# legatus_v0_3.net
KiCad netlist of a schematic drawn in EAGLE
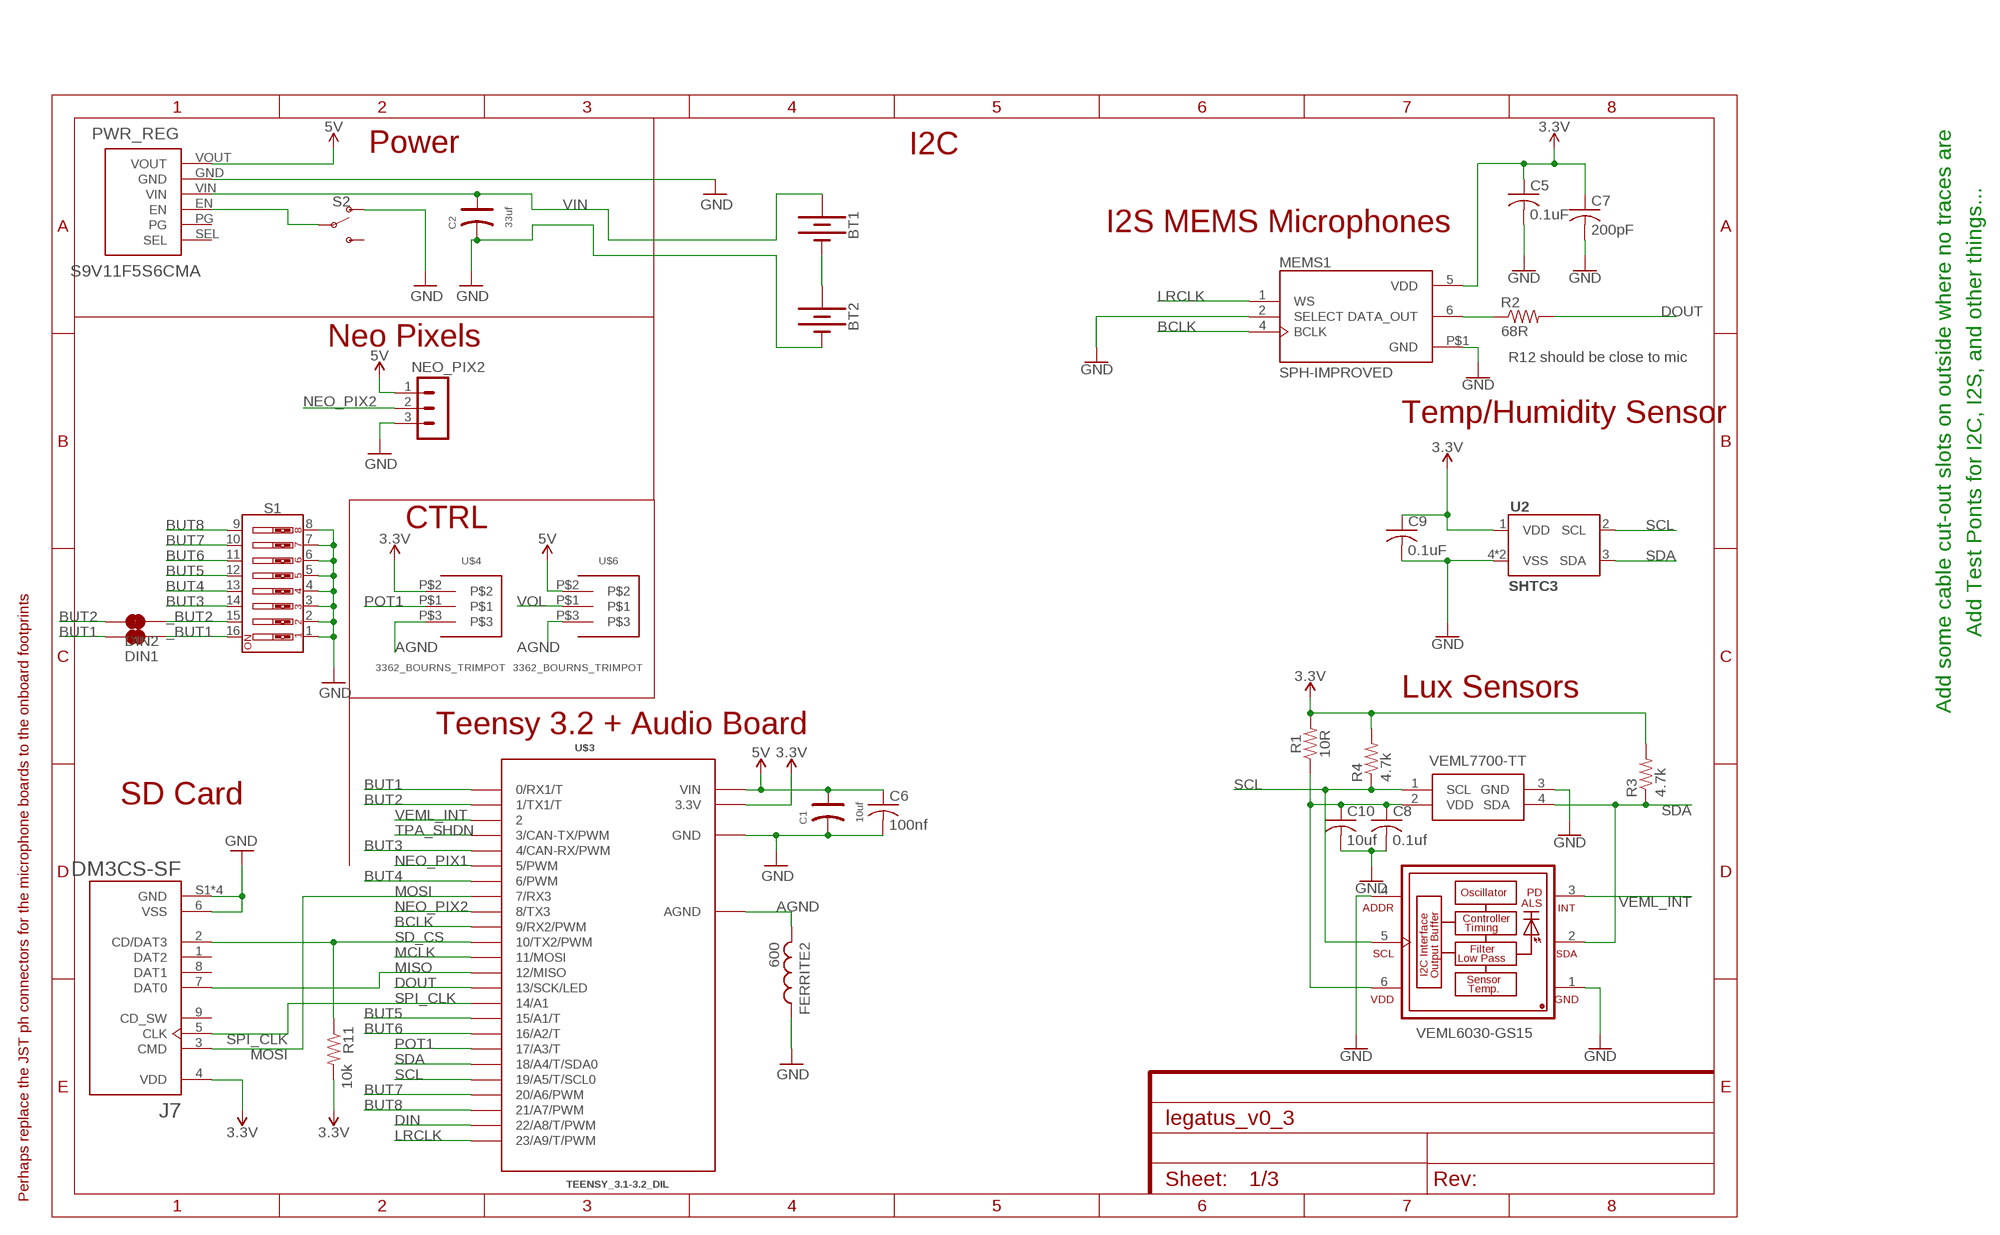
[diagram p0: schematic, sheet 1]
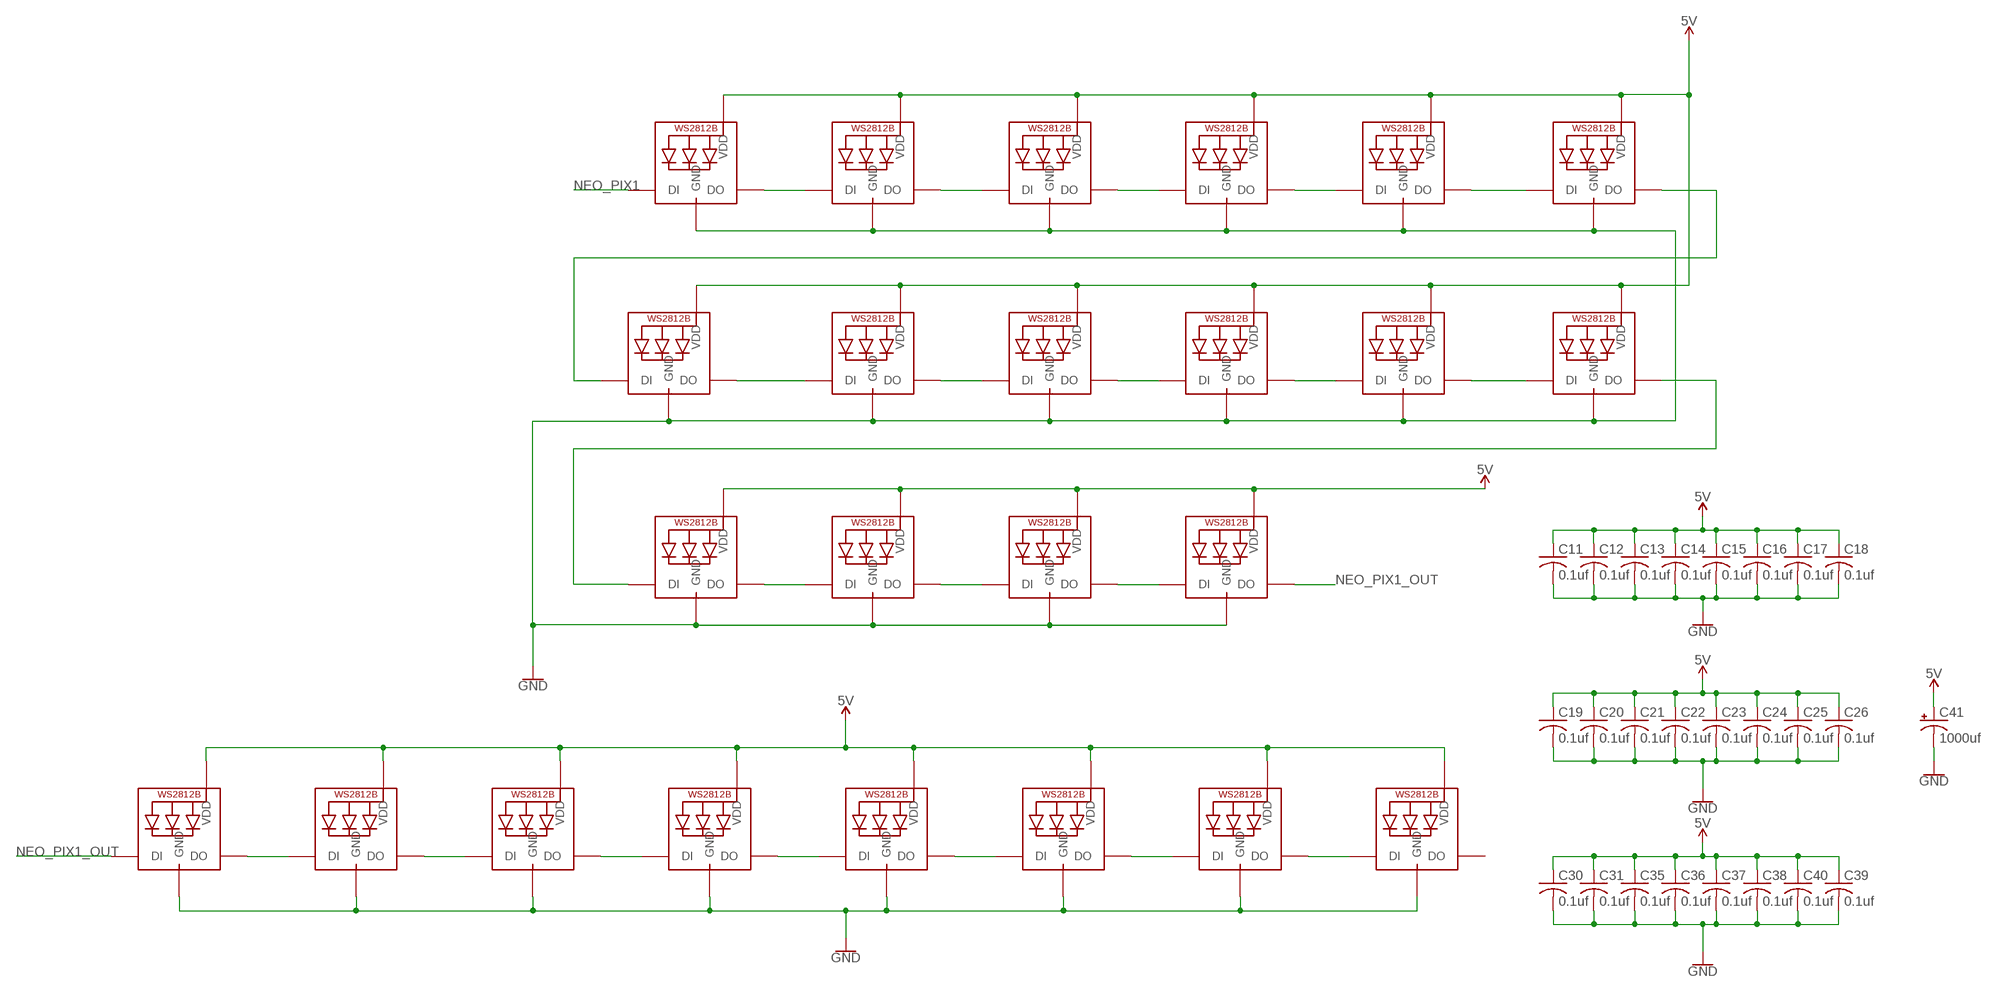
[diagram p1: schematic, sheet 2]
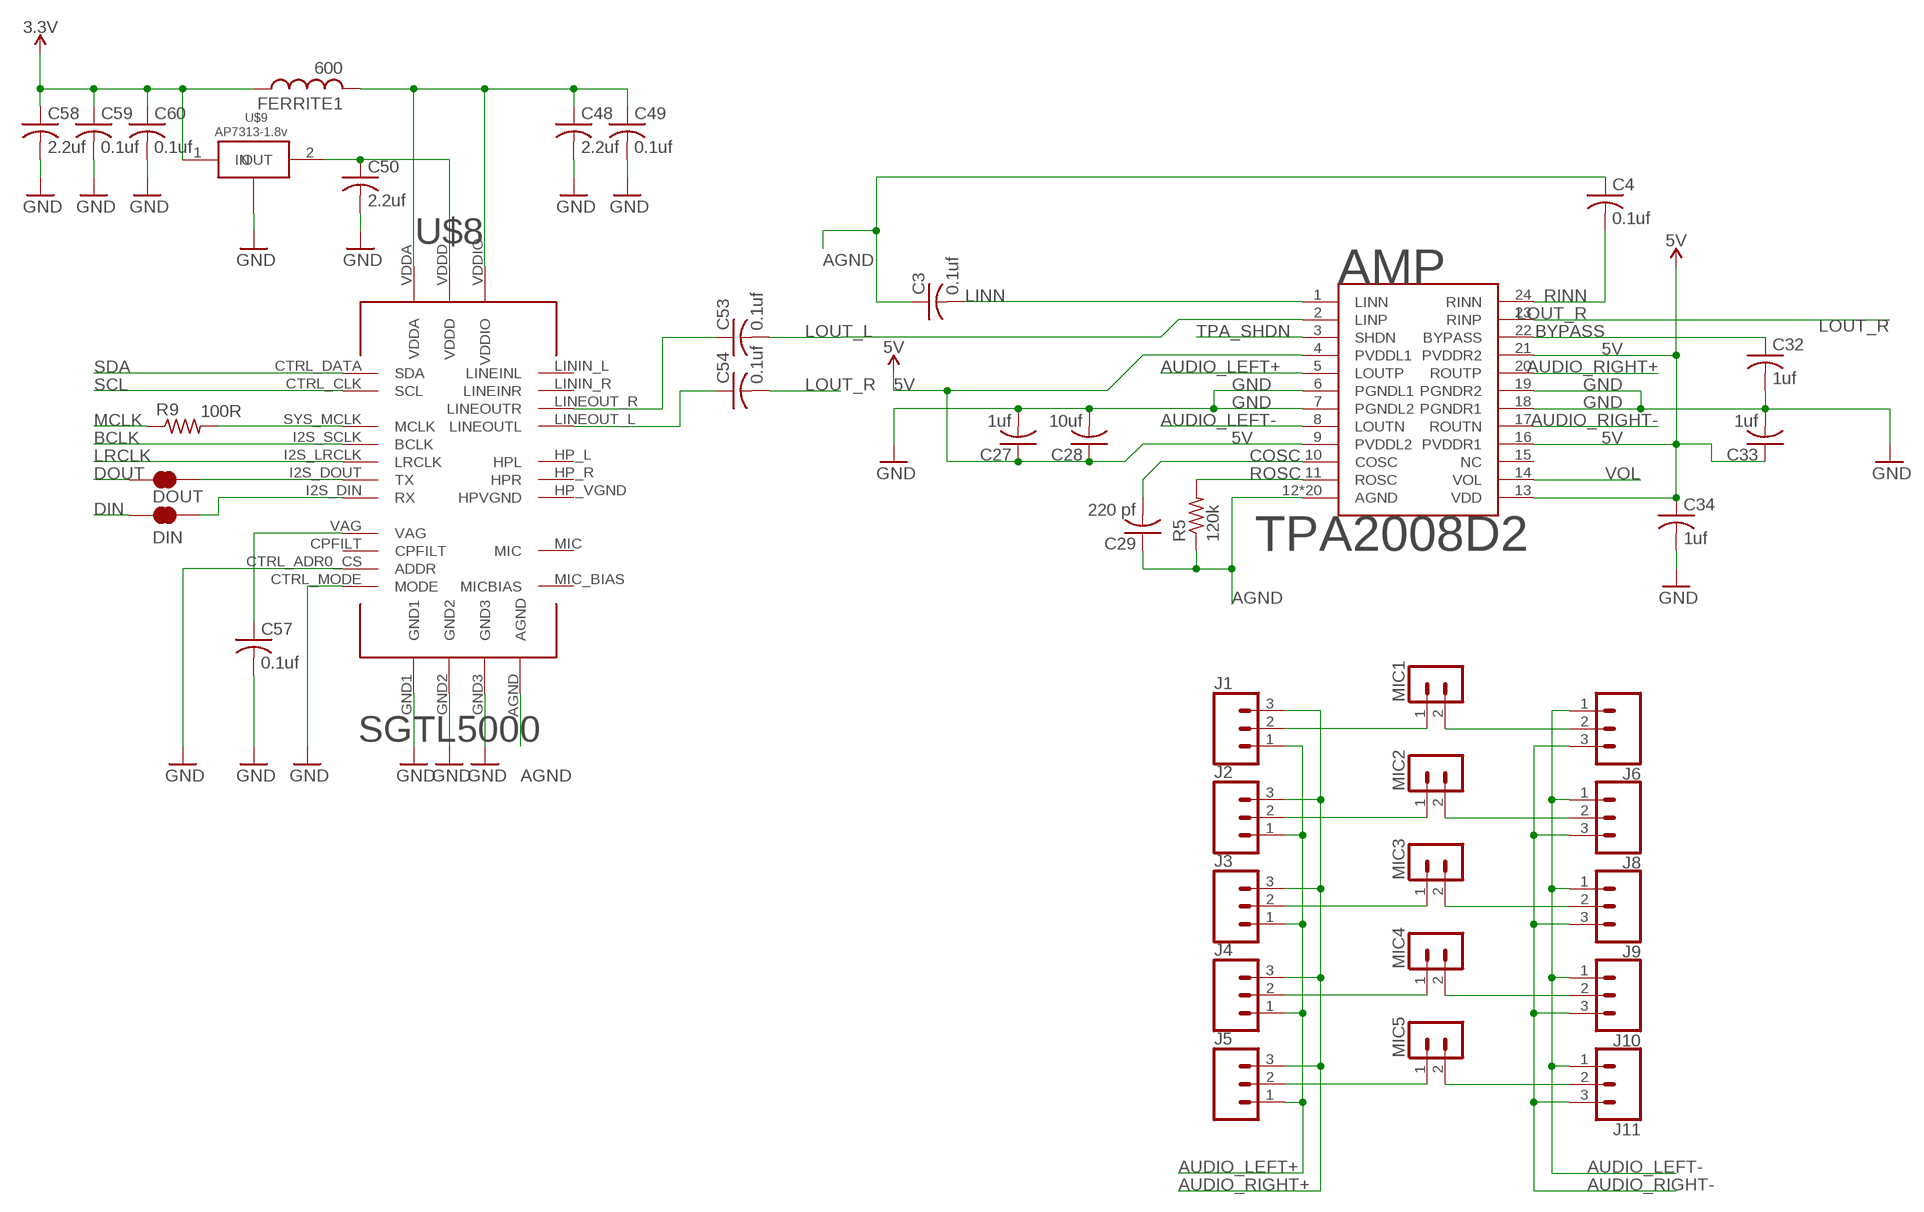
[diagram p2: schematic, sheet 3]

(export (version "E")
  (design (tool "Eeschema 10.0.6"))
  (components
    (comp (ref "AMP")
      (value "TPA2008D2")
      (footprint "eagle-import:PWP-TSSOP24")
      (libsource (lib "eagle-import") (part "TPA2008D2"))
    )
    (comp (ref "C3")
      (value "0.1uf")
      (footprint "eagle-import:C0805")
      (libsource (lib "eagle-import") (part "rcl_334_C-USC0805"))
    )
    (comp (ref "C4")
      (value "0.1uf")
      (footprint "eagle-import:C0805")
      (libsource (lib "eagle-import") (part "rcl_334_C-USC0805"))
    )
    (comp (ref "C27")
      (value "1uf")
      (footprint "eagle-import:C0805")
      (libsource (lib "eagle-import") (part "rcl_334_C-USC0805"))
    )
    (comp (ref "C28")
      (value "10uf")
      (footprint "eagle-import:C0805")
      (libsource (lib "eagle-import") (part "rcl_334_C-USC0805"))
    )
    (comp (ref "C29")
      (value "220 pf")
      (footprint "eagle-import:C0805")
      (libsource (lib "eagle-import") (part "rcl_334_C-USC0805"))
    )
    (comp (ref "C32")
      (value "1uf")
      (footprint "eagle-import:C0805")
      (libsource (lib "eagle-import") (part "rcl_334_C-USC0805"))
    )
    (comp (ref "C33")
      (value "1uf")
      (footprint "eagle-import:C0805")
      (libsource (lib "eagle-import") (part "rcl_334_C-USC0805"))
    )
    (comp (ref "C34")
      (value "1uf")
      (footprint "eagle-import:C0805")
      (libsource (lib "eagle-import") (part "rcl_334_C-USC0805"))
    )
    (comp (ref "C48")
      (value "2.2uf")
      (footprint "eagle-import:C0805")
      (libsource (lib "eagle-import") (part "rcl_334_C-USC0805"))
    )
    (comp (ref "C49")
      (value "0.1uf")
      (footprint "eagle-import:C0805")
      (libsource (lib "eagle-import") (part "rcl_334_C-USC0805"))
    )
    (comp (ref "C50")
      (value "2.2uf")
      (footprint "eagle-import:C0805")
      (libsource (lib "eagle-import") (part "rcl_334_C-USC0805"))
    )
    (comp (ref "C53")
      (value "0.1uf")
      (footprint "eagle-import:C0805")
      (libsource (lib "eagle-import") (part "rcl_334_C-USC0805"))
    )
    (comp (ref "C54")
      (value "0.1uf")
      (footprint "eagle-import:C0805")
      (libsource (lib "eagle-import") (part "rcl_334_C-USC0805"))
    )
    (comp (ref "C57")
      (value "0.1uf")
      (footprint "eagle-import:C0805")
      (libsource (lib "eagle-import") (part "rcl_334_C-USC0805"))
    )
    (comp (ref "C58")
      (value "2.2uf")
      (footprint "eagle-import:C0805")
      (libsource (lib "eagle-import") (part "rcl_334_C-USC0805"))
    )
    (comp (ref "C59")
      (value "0.1uf")
      (footprint "eagle-import:C0805")
      (libsource (lib "eagle-import") (part "rcl_334_C-USC0805"))
    )
    (comp (ref "C60")
      (value "0.1uf")
      (footprint "eagle-import:C0805")
      (libsource (lib "eagle-import") (part "rcl_334_C-USC0805"))
    )
    (comp (ref "DIN")
      (value "JUMPER-SMT_2_NC_TRACE_SILK")
      (footprint "eagle-import:SMT-JUMPER_2_NC_TRACE_SILK")
      (libsource (lib "eagle-import") (part "JUMPER-SMT_2_NC_TRACE_SILK"))
    )
    (comp (ref "DOUT")
      (value "JUMPER-SMT_2_NC_TRACE_SILK")
      (footprint "eagle-import:SMT-JUMPER_2_NC_TRACE_SILK")
      (libsource (lib "eagle-import") (part "JUMPER-SMT_2_NC_TRACE_SILK"))
    )
    (comp (ref "FERRITE1")
      (value "600")
      (footprint "eagle-import:RESC0805_N")
      (libsource (lib "eagle-import") (part "INDUCTOR_0805_N"))
    )
    (comp (ref "J1")
      (value "CONN_03")
      (footprint "eagle-import:1X03")
      (libsource (lib "eagle-import") (part "CONN_03"))
    )
    (comp (ref "J2")
      (value "CONN_03")
      (footprint "eagle-import:1X03")
      (libsource (lib "eagle-import") (part "CONN_03"))
    )
    (comp (ref "J3")
      (value "CONN_03")
      (footprint "eagle-import:1X03")
      (libsource (lib "eagle-import") (part "CONN_03"))
    )
    (comp (ref "J4")
      (value "CONN_03")
      (footprint "eagle-import:1X03")
      (libsource (lib "eagle-import") (part "CONN_03"))
    )
    (comp (ref "J5")
      (value "CONN_03")
      (footprint "eagle-import:1X03")
      (libsource (lib "eagle-import") (part "CONN_03"))
    )
    (comp (ref "J6")
      (value "CONN_03")
      (footprint "eagle-import:1X03")
      (libsource (lib "eagle-import") (part "CONN_03"))
    )
    (comp (ref "J8")
      (value "CONN_03")
      (footprint "eagle-import:1X03")
      (libsource (lib "eagle-import") (part "CONN_03"))
    )
    (comp (ref "J9")
      (value "CONN_03")
      (footprint "eagle-import:1X03")
      (libsource (lib "eagle-import") (part "CONN_03"))
    )
    (comp (ref "J10")
      (value "CONN_03")
      (footprint "eagle-import:1X03")
      (libsource (lib "eagle-import") (part "CONN_03"))
    )
    (comp (ref "J11")
      (value "CONN_03")
      (footprint "eagle-import:1X03")
      (libsource (lib "eagle-import") (part "CONN_03"))
    )
    (comp (ref "MIC1")
      (value "B2B-PH-K")
      (footprint "eagle-import:B2B-PH-K")
      (libsource (lib "eagle-import") (part "B2B-PH-K"))
    )
    (comp (ref "MIC2")
      (value "B2B-PH-K")
      (footprint "eagle-import:B2B-PH-K")
      (libsource (lib "eagle-import") (part "B2B-PH-K"))
    )
    (comp (ref "MIC3")
      (value "B2B-PH-K")
      (footprint "eagle-import:B2B-PH-K")
      (libsource (lib "eagle-import") (part "B2B-PH-K"))
    )
    (comp (ref "MIC4")
      (value "B2B-PH-K")
      (footprint "eagle-import:B2B-PH-K")
      (libsource (lib "eagle-import") (part "B2B-PH-K"))
    )
    (comp (ref "MIC5")
      (value "B2B-PH-K")
      (footprint "eagle-import:B2B-PH-K")
      (libsource (lib "eagle-import") (part "B2B-PH-K"))
    )
    (comp (ref "R5")
      (value "120k")
      (footprint "eagle-import:M0805")
      (libsource (lib "eagle-import") (part "R-US_M0805"))
    )
    (comp (ref "R9")
      (value "100R")
      (footprint "eagle-import:M0805")
      (libsource (lib "eagle-import") (part "rcl_R-US_M0805"))
    )
    (comp (ref "U$8")
      (value "SGTL5000")
      (footprint "eagle-import:QFN-32-5X5MM")
      (libsource (lib "eagle-import") (part "SGTL5000"))
    )
    (comp (ref "U$9")
      (value "AP7313-1.8v")
      (footprint "eagle-import:SOT-23")
      (libsource (lib "eagle-import") (part "AP7313"))
    )
    (comp (ref "C11")
      (value "0.1uf")
      (footprint "eagle-import:C0805")
      (libsource (lib "eagle-import") (part "rcl_334_C-USC0805"))
    )
    (comp (ref "C12")
      (value "0.1uf")
      (footprint "eagle-import:C0805")
      (libsource (lib "eagle-import") (part "rcl_334_C-USC0805"))
    )
    (comp (ref "C13")
      (value "0.1uf")
      (footprint "eagle-import:C0805")
      (libsource (lib "eagle-import") (part "rcl_334_C-USC0805"))
    )
    (comp (ref "C14")
      (value "0.1uf")
      (footprint "eagle-import:C0805")
      (libsource (lib "eagle-import") (part "rcl_334_C-USC0805"))
    )
    (comp (ref "C15")
      (value "0.1uf")
      (footprint "eagle-import:C0805")
      (libsource (lib "eagle-import") (part "rcl_334_C-USC0805"))
    )
    (comp (ref "C16")
      (value "0.1uf")
      (footprint "eagle-import:C0805")
      (libsource (lib "eagle-import") (part "rcl_334_C-USC0805"))
    )
    (comp (ref "C17")
      (value "0.1uf")
      (footprint "eagle-import:C0805")
      (libsource (lib "eagle-import") (part "rcl_334_C-USC0805"))
    )
    (comp (ref "C18")
      (value "0.1uf")
      (footprint "eagle-import:C0805")
      (libsource (lib "eagle-import") (part "rcl_334_C-USC0805"))
    )
    (comp (ref "C19")
      (value "0.1uf")
      (footprint "eagle-import:C0805")
      (libsource (lib "eagle-import") (part "rcl_334_C-USC0805"))
    )
    (comp (ref "C20")
      (value "0.1uf")
      (footprint "eagle-import:C0805")
      (libsource (lib "eagle-import") (part "rcl_334_C-USC0805"))
    )
    (comp (ref "C21")
      (value "0.1uf")
      (footprint "eagle-import:C0805")
      (libsource (lib "eagle-import") (part "rcl_334_C-USC0805"))
    )
    (comp (ref "C22")
      (value "0.1uf")
      (footprint "eagle-import:C0805")
      (libsource (lib "eagle-import") (part "rcl_334_C-USC0805"))
    )
    (comp (ref "C23")
      (value "0.1uf")
      (footprint "eagle-import:C0805")
      (libsource (lib "eagle-import") (part "rcl_334_C-USC0805"))
    )
    (comp (ref "C24")
      (value "0.1uf")
      (footprint "eagle-import:C0805")
      (libsource (lib "eagle-import") (part "rcl_334_C-USC0805"))
    )
    (comp (ref "C25")
      (value "0.1uf")
      (footprint "eagle-import:C0805")
      (libsource (lib "eagle-import") (part "rcl_334_C-USC0805"))
    )
    (comp (ref "C26")
      (value "0.1uf")
      (footprint "eagle-import:C0805")
      (libsource (lib "eagle-import") (part "rcl_334_C-USC0805"))
    )
    (comp (ref "C30")
      (value "0.1uf")
      (footprint "eagle-import:C0805")
      (libsource (lib "eagle-import") (part "rcl_334_C-USC0805"))
    )
    (comp (ref "C31")
      (value "0.1uf")
      (footprint "eagle-import:C0805")
      (libsource (lib "eagle-import") (part "rcl_334_C-USC0805"))
    )
    (comp (ref "C35")
      (value "0.1uf")
      (footprint "eagle-import:C0805")
      (libsource (lib "eagle-import") (part "rcl_334_C-USC0805"))
    )
    (comp (ref "C36")
      (value "0.1uf")
      (footprint "eagle-import:C0805")
      (libsource (lib "eagle-import") (part "rcl_334_C-USC0805"))
    )
    (comp (ref "C37")
      (value "0.1uf")
      (footprint "eagle-import:C0805")
      (libsource (lib "eagle-import") (part "rcl_334_C-USC0805"))
    )
    (comp (ref "C38")
      (value "0.1uf")
      (footprint "eagle-import:C0805")
      (libsource (lib "eagle-import") (part "rcl_334_C-USC0805"))
    )
    (comp (ref "C39")
      (value "0.1uf")
      (footprint "eagle-import:C0805")
      (libsource (lib "eagle-import") (part "rcl_334_C-USC0805"))
    )
    (comp (ref "C40")
      (value "0.1uf")
      (footprint "eagle-import:C0805")
      (libsource (lib "eagle-import") (part "rcl_334_C-USC0805"))
    )
    (comp (ref "C41")
      (value "1000uf")
      (footprint "eagle-import:153CLV-1010")
      (libsource (lib "eagle-import") (part "CPOL-US153CLV-1010"))
    )
    (comp (ref "LED1")
      (value "WS2812B_5050N")
      (footprint "eagle-import:WS2812B-NARROW")
      (libsource (lib "eagle-import") (part "WS2812B_5050N"))
    )
    (comp (ref "LED2")
      (value "WS2812B_5050N")
      (footprint "eagle-import:WS2812B-NARROW")
      (libsource (lib "eagle-import") (part "WS2812B_5050N"))
    )
    (comp (ref "LED3")
      (value "WS2812B_5050N")
      (footprint "eagle-import:WS2812B-NARROW")
      (libsource (lib "eagle-import") (part "WS2812B_5050N"))
    )
    (comp (ref "LED4")
      (value "WS2812B_5050N")
      (footprint "eagle-import:WS2812B-NARROW")
      (libsource (lib "eagle-import") (part "WS2812B_5050N"))
    )
    (comp (ref "LED5")
      (value "WS2812B_5050N")
      (footprint "eagle-import:WS2812B-NARROW")
      (libsource (lib "eagle-import") (part "WS2812B_5050N"))
    )
    (comp (ref "LED6")
      (value "WS2812B_5050N")
      (footprint "eagle-import:WS2812B-NARROW")
      (libsource (lib "eagle-import") (part "WS2812B_5050N"))
    )
    (comp (ref "LED7")
      (value "WS2812B_5050N")
      (footprint "eagle-import:WS2812B-NARROW")
      (libsource (lib "eagle-import") (part "WS2812B_5050N"))
    )
    (comp (ref "LED8")
      (value "WS2812B_5050N")
      (footprint "eagle-import:WS2812B-NARROW")
      (libsource (lib "eagle-import") (part "WS2812B_5050N"))
    )
    (comp (ref "LED9")
      (value "WS2812B_5050N")
      (footprint "eagle-import:WS2812B-NARROW")
      (libsource (lib "eagle-import") (part "WS2812B_5050N"))
    )
    (comp (ref "LED10")
      (value "WS2812B_5050N")
      (footprint "eagle-import:WS2812B-NARROW")
      (libsource (lib "eagle-import") (part "WS2812B_5050N"))
    )
    (comp (ref "LED11")
      (value "WS2812B_5050N")
      (footprint "eagle-import:WS2812B-NARROW")
      (libsource (lib "eagle-import") (part "WS2812B_5050N"))
    )
    (comp (ref "LED12")
      (value "WS2812B_5050N")
      (footprint "eagle-import:WS2812B-NARROW")
      (libsource (lib "eagle-import") (part "WS2812B_5050N"))
    )
    (comp (ref "LED13")
      (value "WS2812B_5050N")
      (footprint "eagle-import:WS2812B-NARROW")
      (libsource (lib "eagle-import") (part "WS2812B_5050N"))
    )
    (comp (ref "LED14")
      (value "WS2812B_5050N")
      (footprint "eagle-import:WS2812B-NARROW")
      (libsource (lib "eagle-import") (part "WS2812B_5050N"))
    )
    (comp (ref "LED15")
      (value "WS2812B_5050N")
      (footprint "eagle-import:WS2812B-NARROW")
      (libsource (lib "eagle-import") (part "WS2812B_5050N"))
    )
    (comp (ref "LED16")
      (value "WS2812B_5050N")
      (footprint "eagle-import:WS2812B-NARROW")
      (libsource (lib "eagle-import") (part "WS2812B_5050N"))
    )
    (comp (ref "LED17")
      (value "WS2812B_5050N")
      (footprint "eagle-import:WS2812B-NARROW")
      (libsource (lib "eagle-import") (part "WS2812B_5050N"))
    )
    (comp (ref "LED18")
      (value "WS2812B_5050N")
      (footprint "eagle-import:WS2812B-NARROW")
      (libsource (lib "eagle-import") (part "WS2812B_5050N"))
    )
    (comp (ref "LED19")
      (value "WS2812B_5050N")
      (footprint "eagle-import:WS2812B-NARROW")
      (libsource (lib "eagle-import") (part "WS2812B_5050N"))
    )
    (comp (ref "LED20")
      (value "WS2812B_5050N")
      (footprint "eagle-import:WS2812B-NARROW")
      (libsource (lib "eagle-import") (part "WS2812B_5050N"))
    )
    (comp (ref "LED21")
      (value "WS2812B_5050N")
      (footprint "eagle-import:WS2812B-NARROW")
      (libsource (lib "eagle-import") (part "WS2812B_5050N"))
    )
    (comp (ref "LED22")
      (value "WS2812B_5050N")
      (footprint "eagle-import:WS2812B-NARROW")
      (libsource (lib "eagle-import") (part "WS2812B_5050N"))
    )
    (comp (ref "LED23")
      (value "WS2812B_5050N")
      (footprint "eagle-import:WS2812B-NARROW")
      (libsource (lib "eagle-import") (part "WS2812B_5050N"))
    )
    (comp (ref "LED24")
      (value "WS2812B_5050N")
      (footprint "eagle-import:WS2812B-NARROW")
      (libsource (lib "eagle-import") (part "WS2812B_5050N"))
    )
    (comp (ref "BT1")
      (value "BATTERY-18650")
      (footprint "eagle-import:BATTERY_18650-HOLDER")
      (libsource (lib "eagle-import") (part "BATTERY-18650"))
    )
    (comp (ref "BT2")
      (value "BATTERY-18650")
      (footprint "eagle-import:BATTERY_18650-HOLDER")
      (libsource (lib "eagle-import") (part "BATTERY-18650"))
    )
    (comp (ref "C1")
      (value "10uf")
      (footprint "eagle-import:PC-D5.3MM")
      (fields (field (name "MPN") "KS 100uF/16V"))
      (libsource (lib "eagle-import") (part "DIP-ALUMINUM-47UF-16V(D5-H7MM)"))
    )
    (comp (ref "C2")
      (value "33uf")
      (footprint "eagle-import:PC-D5.3MM")
      (fields (field (name "MPN") "KS 100uF/16V"))
      (libsource (lib "eagle-import") (part "DIP-ALUMINUM-47UF-16V(D5-H7MM)"))
    )
    (comp (ref "C5")
      (value "0.1uF")
      (footprint "eagle-import:C0805")
      (libsource (lib "eagle-import") (part "rcl_334_C-USC0805"))
    )
    (comp (ref "C6")
      (value "100nf")
      (footprint "eagle-import:C2012")
      (libsource (lib "eagle-import") (part "C-USC2012"))
    )
    (comp (ref "C7")
      (value "200pF")
      (footprint "eagle-import:C0805")
      (libsource (lib "eagle-import") (part "rcl_334_C-USC0805"))
    )
    (comp (ref "C8")
      (value "0.1uf")
      (footprint "eagle-import:C0805")
      (libsource (lib "eagle-import") (part "rcl_334_C-USC0805"))
    )
    (comp (ref "C9")
      (value "0.1uF")
      (footprint "eagle-import:C0805")
      (libsource (lib "eagle-import") (part "rcl_334_C-USC0805"))
    )
    (comp (ref "C10")
      (value "10uf")
      (footprint "eagle-import:C0805")
      (libsource (lib "eagle-import") (part "rcl_334_C-USC0805"))
    )
    (comp (ref "DIN1")
      (value "JUMPER-SMT_2_NC_TRACE_SILK")
      (footprint "eagle-import:SMT-JUMPER_2_NC_TRACE_SILK")
      (libsource (lib "eagle-import") (part "JUMPER-SMT_2_NC_TRACE_SILK"))
    )
    (comp (ref "DIN2")
      (value "JUMPER-SMT_2_NC_TRACE_SILK")
      (footprint "eagle-import:SMT-JUMPER_2_NC_TRACE_SILK")
      (libsource (lib "eagle-import") (part "JUMPER-SMT_2_NC_TRACE_SILK"))
    )
    (comp (ref "FERRITE2")
      (value "600")
      (footprint "eagle-import:RESC0805_N")
      (libsource (lib "eagle-import") (part "INDUCTOR_0805_N"))
    )
    (comp (ref "J7")
      (value "DM3CS-SF")
      (footprint "eagle-import:HRS_DM3CS-SF")
      (fields (field (name "MF") "Hirose"))
      (libsource (lib "eagle-import") (part "DM3CS-SF"))
    )
    (comp (ref "MEMS1")
      (value "SPH-IMPROVED")
      (footprint "eagle-import:MIC_SPH0645LM4H-B_LARGER_RING")
      (libsource (lib "eagle-import") (part "SPH-IMPROVED"))
    )
    (comp (ref "NEO_PIX2")
      (value "B3B-PH-K")
      (footprint "eagle-import:B3B-PH-K")
      (libsource (lib "eagle-import") (part "B3B-PH-K"))
    )
    (comp (ref "PWR_REG")
      (value "S9V11F5S6CMA")
      (footprint "eagle-import:S9V11F3S5CMA")
      (libsource (lib "eagle-import") (part "S9V11F5S6CMA"))
    )
    (comp (ref "R1")
      (value "10R")
      (footprint "eagle-import:R0805")
      (libsource (lib "eagle-import") (part "audio amplifier example_970892_R-US_R0805"))
    )
    (comp (ref "R2")
      (value "68R")
      (footprint "eagle-import:M0805")
      (libsource (lib "eagle-import") (part "R-US_M0805"))
    )
    (comp (ref "R3")
      (value "4.7k")
      (footprint "eagle-import:M0805")
      (libsource (lib "eagle-import") (part "R-US_M0805"))
    )
    (comp (ref "R4")
      (value "4.7k")
      (footprint "eagle-import:M0805")
      (libsource (lib "eagle-import") (part "R-US_M0805"))
    )
    (comp (ref "R11")
      (value "10k")
      (footprint "eagle-import:M0805")
      (libsource (lib "eagle-import") (part "rcl_R-US_M0805"))
    )
    (comp (ref "S1")
      (value "DIP-08-PTH")
      (footprint "eagle-import:DIPSWITCH-08")
      (libsource (lib "eagle-import") (part "DIP-08-PTH"))
    )
    (comp (ref "S2")
      (value "SWITCH-SPDT-PTH-11.6X4.0MM-LOCK")
      (footprint "eagle-import:SWITCH_SPDT_PTH_11.6X4.0MM_LOCK")
      (libsource (lib "eagle-import") (part "SWITCH-SPDT-PTH-11.6X4.0MM-LOCK"))
    )
    (comp (ref "U$3")
      (value "TEENSY_3.1-3.2_DIL")
      (footprint "eagle-import:TEENSY_3.0-3.2&LC_DIL")
      (libsource (lib "eagle-import") (part "TEENSY_3.1-3.2_DIL"))
    )
    (comp (ref "U$4")
      (value "3362_BOURNS_TRIMPOT")
      (footprint "eagle-import:3362_BOURNS_TRIMPOT")
      (libsource (lib "eagle-import") (part "3362_BOURNS_TRIMPOT"))
    )
    (comp (ref "U$6")
      (value "3362_BOURNS_TRIMPOT")
      (footprint "eagle-import:3362_BOURNS_TRIMPOT")
      (libsource (lib "eagle-import") (part "3362_BOURNS_TRIMPOT"))
    )
    (comp (ref "U2")
      (value "SHTC3")
      (footprint "eagle-import:SHTC3")
      (libsource (lib "eagle-import") (part "SHTC3"))
    )
    (comp (ref "VEML1")
      (value "VEML7700-TT")
      (footprint "eagle-import:VEML7700")
      (fields (field (name "MOUSER_PART_NUMBER") "78-VEML7700-TT") (field (name "RS_PART_NUMBER") "1226791P"))
      (libsource (lib "eagle-import") (part "VEML7700-TT"))
    )
    (comp (ref "VMEL1")
      (value "VEML6030-GS15")
      (footprint "eagle-import:VISHAY_VEML6030_2X2X0.87")
      (fields (field (name "MF") "Vishay Semiconductor"))
      (libsource (lib "eagle-import") (part "VEML6030-GS15"))
    )
  )
  (nets
    (net (code "1") (name "3.3V") (class "Default")
      (node (ref "C5") (pin "1") (pinfunction "1_1") (pintype "passive"))
      (node (ref "C58") (pin "1") (pinfunction "1_1") (pintype "passive"))
      (node (ref "C59") (pin "1") (pinfunction "1_1") (pintype "passive"))
      (node (ref "C60") (pin "1") (pinfunction "1_1") (pintype "passive"))
      (node (ref "C7") (pin "1") (pinfunction "1_1") (pintype "passive"))
      (node (ref "C9") (pin "1") (pinfunction "1_1") (pintype "passive"))
      (node (ref "FERRITE1") (pin "1") (pinfunction "1_1") (pintype "passive"))
      (node (ref "J7") (pin "4") (pinfunction "VDD_4") (pintype "passive"))
      (node (ref "MEMS1") (pin "5") (pinfunction "VDD_5") (pintype "power_in"))
      (node (ref "R1") (pin "2") (pinfunction "2_2") (pintype "passive"))
      (node (ref "R11") (pin "2") (pinfunction "2_2") (pintype "passive"))
      (node (ref "R3") (pin "2") (pinfunction "2_2") (pintype "passive"))
      (node (ref "R4") (pin "2") (pinfunction "2_2") (pintype "passive"))
      (node (ref "U$3") (pin "3.3V") (pinfunction "3.3V_3.3V") (pintype "power_in"))
      (node (ref "U$4") (pin "P$2") (pinfunction "P$2_P$2") (pintype "bidirectional"))
      (node (ref "U$9") (pin "1") (pinfunction "IN_1") (pintype "bidirectional"))
      (node (ref "U2") (pin "1") (pinfunction "VDD_1") (pintype "bidirectional"))
    )
    (net (code "2") (name "5V") (class "Default")
      (node (ref "AMP") (pin "13") (pinfunction "VDD_13") (pintype "bidirectional"))
      (node (ref "AMP") (pin "16") (pinfunction "PVDDR1_16") (pintype "bidirectional"))
      (node (ref "AMP") (pin "21") (pinfunction "PVDDR2_21") (pintype "bidirectional"))
      (node (ref "AMP") (pin "4") (pinfunction "PVDDL1_4") (pintype "bidirectional"))
      (node (ref "AMP") (pin "9") (pinfunction "PVDDL2_9") (pintype "bidirectional"))
      (node (ref "C1") (pin "+") (pinfunction "+_+") (pintype "passive"))
      (node (ref "C11") (pin "1") (pinfunction "1_1") (pintype "passive"))
      (node (ref "C12") (pin "1") (pinfunction "1_1") (pintype "passive"))
      (node (ref "C13") (pin "1") (pinfunction "1_1") (pintype "passive"))
      (node (ref "C14") (pin "1") (pinfunction "1_1") (pintype "passive"))
      (node (ref "C15") (pin "1") (pinfunction "1_1") (pintype "passive"))
      (node (ref "C16") (pin "1") (pinfunction "1_1") (pintype "passive"))
      (node (ref "C17") (pin "1") (pinfunction "1_1") (pintype "passive"))
      (node (ref "C18") (pin "1") (pinfunction "1_1") (pintype "passive"))
      (node (ref "C19") (pin "1") (pinfunction "1_1") (pintype "passive"))
      (node (ref "C20") (pin "1") (pinfunction "1_1") (pintype "passive"))
      (node (ref "C21") (pin "1") (pinfunction "1_1") (pintype "passive"))
      (node (ref "C22") (pin "1") (pinfunction "1_1") (pintype "passive"))
      (node (ref "C23") (pin "1") (pinfunction "1_1") (pintype "passive"))
      (node (ref "C24") (pin "1") (pinfunction "1_1") (pintype "passive"))
      (node (ref "C25") (pin "1") (pinfunction "1_1") (pintype "passive"))
      (node (ref "C26") (pin "1") (pinfunction "1_1") (pintype "passive"))
      (node (ref "C27") (pin "1") (pinfunction "1_1") (pintype "passive"))
      (node (ref "C28") (pin "1") (pinfunction "1_1") (pintype "passive"))
      (node (ref "C30") (pin "1") (pinfunction "1_1") (pintype "passive"))
      (node (ref "C31") (pin "1") (pinfunction "1_1") (pintype "passive"))
      (node (ref "C33") (pin "1") (pinfunction "1_1") (pintype "passive"))
      (node (ref "C34") (pin "1") (pinfunction "1_1") (pintype "passive"))
      (node (ref "C35") (pin "1") (pinfunction "1_1") (pintype "passive"))
      (node (ref "C36") (pin "1") (pinfunction "1_1") (pintype "passive"))
      (node (ref "C37") (pin "1") (pinfunction "1_1") (pintype "passive"))
      (node (ref "C38") (pin "1") (pinfunction "1_1") (pintype "passive"))
      (node (ref "C39") (pin "1") (pinfunction "1_1") (pintype "passive"))
      (node (ref "C40") (pin "1") (pinfunction "1_1") (pintype "passive"))
      (node (ref "C41") (pin "+") (pinfunction "+_+") (pintype "passive"))
      (node (ref "C6") (pin "1") (pinfunction "1_1") (pintype "passive"))
      (node (ref "LED1") (pin "1-VDD") (pinfunction "VDD_1-VDD") (pintype "power_in"))
      (node (ref "LED10") (pin "1-VDD") (pinfunction "VDD_1-VDD") (pintype "power_in"))
      (node (ref "LED11") (pin "1-VDD") (pinfunction "VDD_1-VDD") (pintype "power_in"))
      (node (ref "LED12") (pin "1-VDD") (pinfunction "VDD_1-VDD") (pintype "power_in"))
      (node (ref "LED13") (pin "1-VDD") (pinfunction "VDD_1-VDD") (pintype "power_in"))
      (node (ref "LED14") (pin "1-VDD") (pinfunction "VDD_1-VDD") (pintype "power_in"))
      (node (ref "LED15") (pin "1-VDD") (pinfunction "VDD_1-VDD") (pintype "power_in"))
      (node (ref "LED16") (pin "1-VDD") (pinfunction "VDD_1-VDD") (pintype "power_in"))
      (node (ref "LED17") (pin "1-VDD") (pinfunction "VDD_1-VDD") (pintype "power_in"))
      (node (ref "LED18") (pin "1-VDD") (pinfunction "VDD_1-VDD") (pintype "power_in"))
      (node (ref "LED19") (pin "1-VDD") (pinfunction "VDD_1-VDD") (pintype "power_in"))
      (node (ref "LED2") (pin "1-VDD") (pinfunction "VDD_1-VDD") (pintype "power_in"))
      (node (ref "LED20") (pin "1-VDD") (pinfunction "VDD_1-VDD") (pintype "power_in"))
      (node (ref "LED21") (pin "1-VDD") (pinfunction "VDD_1-VDD") (pintype "power_in"))
      (node (ref "LED22") (pin "1-VDD") (pinfunction "VDD_1-VDD") (pintype "power_in"))
      (node (ref "LED23") (pin "1-VDD") (pinfunction "VDD_1-VDD") (pintype "power_in"))
      (node (ref "LED24") (pin "1-VDD") (pinfunction "VDD_1-VDD") (pintype "power_in"))
      (node (ref "LED3") (pin "1-VDD") (pinfunction "VDD_1-VDD") (pintype "power_in"))
      (node (ref "LED4") (pin "1-VDD") (pinfunction "VDD_1-VDD") (pintype "power_in"))
      (node (ref "LED5") (pin "1-VDD") (pinfunction "VDD_1-VDD") (pintype "power_in"))
      (node (ref "LED6") (pin "1-VDD") (pinfunction "VDD_1-VDD") (pintype "power_in"))
      (node (ref "LED7") (pin "1-VDD") (pinfunction "VDD_1-VDD") (pintype "power_in"))
      (node (ref "LED8") (pin "1-VDD") (pinfunction "VDD_1-VDD") (pintype "power_in"))
      (node (ref "LED9") (pin "1-VDD") (pinfunction "VDD_1-VDD") (pintype "power_in"))
      (node (ref "NEO_PIX2") (pin "1") (pinfunction "1_1") (pintype "passive"))
      (node (ref "PWR_REG") (pin "VOUT") (pinfunction "VOUT_VOUT") (pintype "bidirectional"))
      (node (ref "U$3") (pin "VIN") (pinfunction "VIN_VIN") (pintype "power_in"))
      (node (ref "U$6") (pin "P$2") (pinfunction "P$2_P$2") (pintype "bidirectional"))
    )
    (net (code "3") (name "AGND") (class "Default")
      (node (ref "AMP") (pin "12") (pinfunction "AGND_12") (pintype "bidirectional"))
      (node (ref "AMP") (pin "EXP") (pinfunction "AGND_EXP") (pintype "bidirectional"))
      (node (ref "AMP") (pin "EXP@1") (pinfunction "AGND_EXP@1") (pintype "bidirectional"))
      (node (ref "AMP") (pin "EXP@10") (pinfunction "AGND_EXP@10") (pintype "bidirectional"))
      (node (ref "AMP") (pin "EXP@11") (pinfunction "AGND_EXP@11") (pintype "bidirectional"))
      (node (ref "AMP") (pin "EXP@12") (pinfunction "AGND_EXP@12") (pintype "bidirectional"))
      (node (ref "AMP") (pin "EXP@13") (pinfunction "AGND_EXP@13") (pintype "bidirectional"))
      (node (ref "AMP") (pin "EXP@14") (pinfunction "AGND_EXP@14") (pintype "bidirectional"))
      (node (ref "AMP") (pin "EXP@15") (pinfunction "AGND_EXP@15") (pintype "bidirectional"))
      (node (ref "AMP") (pin "EXP@16") (pinfunction "AGND_EXP@16") (pintype "bidirectional"))
      (node (ref "AMP") (pin "EXP@17") (pinfunction "AGND_EXP@17") (pintype "bidirectional"))
      (node (ref "AMP") (pin "EXP@18") (pinfunction "AGND_EXP@18") (pintype "bidirectional"))
      (node (ref "AMP") (pin "EXP@2") (pinfunction "AGND_EXP@2") (pintype "bidirectional"))
      (node (ref "AMP") (pin "EXP@3") (pinfunction "AGND_EXP@3") (pintype "bidirectional"))
      (node (ref "AMP") (pin "EXP@4") (pinfunction "AGND_EXP@4") (pintype "bidirectional"))
      (node (ref "AMP") (pin "EXP@5") (pinfunction "AGND_EXP@5") (pintype "bidirectional"))
      (node (ref "AMP") (pin "EXP@6") (pinfunction "AGND_EXP@6") (pintype "bidirectional"))
      (node (ref "AMP") (pin "EXP@7") (pinfunction "AGND_EXP@7") (pintype "bidirectional"))
      (node (ref "AMP") (pin "EXP@8") (pinfunction "AGND_EXP@8") (pintype "bidirectional"))
      (node (ref "AMP") (pin "EXP@9") (pinfunction "AGND_EXP@9") (pintype "bidirectional"))
      (node (ref "C29") (pin "1") (pinfunction "1_1") (pintype "passive"))
      (node (ref "C3") (pin "1") (pinfunction "1_1") (pintype "passive"))
      (node (ref "C4") (pin "1") (pinfunction "1_1") (pintype "passive"))
      (node (ref "FERRITE2") (pin "2") (pinfunction "2_2") (pintype "passive"))
      (node (ref "R5") (pin "1") (pinfunction "1_1") (pintype "passive"))
      (node (ref "U$3") (pin "AGND") (pinfunction "AGND_AGND") (pintype "power_in"))
      (node (ref "U$4") (pin "P$3") (pinfunction "P$3_P$3") (pintype "bidirectional"))
      (node (ref "U$6") (pin "P$3") (pinfunction "P$3_P$3") (pintype "bidirectional"))
      (node (ref "U$8") (pin "AGND") (pinfunction "AGND_AGND") (pintype "bidirectional"))
    )
    (net (code "4") (name "AUDIO_LEFT+") (class "Default")
      (node (ref "AMP") (pin "5") (pinfunction "LOUTP_5") (pintype "bidirectional"))
      (node (ref "J1") (pin "1") (pinfunction "1_1") (pintype "passive"))
      (node (ref "J2") (pin "1") (pinfunction "1_1") (pintype "passive"))
      (node (ref "J3") (pin "1") (pinfunction "1_1") (pintype "passive"))
      (node (ref "J4") (pin "1") (pinfunction "1_1") (pintype "passive"))
      (node (ref "J5") (pin "1") (pinfunction "1_1") (pintype "passive"))
    )
    (net (code "5") (name "AUDIO_LEFT-") (class "Default")
      (node (ref "AMP") (pin "8") (pinfunction "LOUTN_8") (pintype "bidirectional"))
      (node (ref "J10") (pin "1") (pinfunction "1_1") (pintype "passive"))
      (node (ref "J11") (pin "1") (pinfunction "1_1") (pintype "passive"))
      (node (ref "J6") (pin "1") (pinfunction "1_1") (pintype "passive"))
      (node (ref "J8") (pin "1") (pinfunction "1_1") (pintype "passive"))
      (node (ref "J9") (pin "1") (pinfunction "1_1") (pintype "passive"))
    )
    (net (code "6") (name "AUDIO_RIGHT+") (class "Default")
      (node (ref "AMP") (pin "20") (pinfunction "ROUTP_20") (pintype "bidirectional"))
      (node (ref "J1") (pin "3") (pinfunction "3_3") (pintype "passive"))
      (node (ref "J2") (pin "3") (pinfunction "3_3") (pintype "passive"))
      (node (ref "J3") (pin "3") (pinfunction "3_3") (pintype "passive"))
      (node (ref "J4") (pin "3") (pinfunction "3_3") (pintype "passive"))
      (node (ref "J5") (pin "3") (pinfunction "3_3") (pintype "passive"))
    )
    (net (code "7") (name "AUDIO_RIGHT-") (class "Default")
      (node (ref "AMP") (pin "17") (pinfunction "ROUTN_17") (pintype "bidirectional"))
      (node (ref "J10") (pin "3") (pinfunction "3_3") (pintype "passive"))
      (node (ref "J11") (pin "3") (pinfunction "3_3") (pintype "passive"))
      (node (ref "J6") (pin "3") (pinfunction "3_3") (pintype "passive"))
      (node (ref "J8") (pin "3") (pinfunction "3_3") (pintype "passive"))
      (node (ref "J9") (pin "3") (pinfunction "3_3") (pintype "passive"))
    )
    (net (code "8") (name "BCLK") (class "Default")
      (node (ref "MEMS1") (pin "4") (pinfunction "BCLK_4") (pintype "input"))
      (node (ref "U$3") (pin "9") (pinfunction "9/RX2/PWM_9") (pintype "bidirectional"))
      (node (ref "U$8") (pin "I2S_SCLK") (pinfunction "BCLK_I2S_SCLK") (pintype "bidirectional"))
    )
    (net (code "9") (name "BUT1") (class "Default")
      (node (ref "DIN1") (pin "1") (pinfunction "1_1") (pintype "passive"))
      (node (ref "U$3") (pin "0") (pinfunction "0/RX1/T_0") (pintype "bidirectional"))
    )
    (net (code "10") (name "BUT2") (class "Default")
      (node (ref "DIN2") (pin "1") (pinfunction "1_1") (pintype "passive"))
      (node (ref "U$3") (pin "1") (pinfunction "1/TX1/T_1") (pintype "bidirectional"))
    )
    (net (code "11") (name "BUT3") (class "Default")
      (node (ref "S1") (pin "14") (pinfunction "14_14") (pintype "passive"))
      (node (ref "U$3") (pin "4") (pinfunction "4/CAN-RX/PWM_4") (pintype "bidirectional"))
    )
    (net (code "12") (name "BUT4") (class "Default")
      (node (ref "S1") (pin "13") (pinfunction "13_13") (pintype "passive"))
      (node (ref "U$3") (pin "6") (pinfunction "6/PWM_6") (pintype "bidirectional"))
    )
    (net (code "13") (name "BUT5") (class "Default")
      (node (ref "S1") (pin "12") (pinfunction "12_12") (pintype "passive"))
      (node (ref "U$3") (pin "15/A1") (pinfunction "15/A1/T_15/A1") (pintype "bidirectional"))
    )
    (net (code "14") (name "BUT6") (class "Default")
      (node (ref "S1") (pin "11") (pinfunction "11_11") (pintype "passive"))
      (node (ref "U$3") (pin "16/A2") (pinfunction "16/A2/T_16/A2") (pintype "bidirectional"))
    )
    (net (code "15") (name "BUT7") (class "Default")
      (node (ref "S1") (pin "10") (pinfunction "10_10") (pintype "passive"))
      (node (ref "U$3") (pin "20/A6") (pinfunction "20/A6/PWM_20/A6") (pintype "bidirectional"))
    )
    (net (code "16") (name "BUT8") (class "Default")
      (node (ref "S1") (pin "9") (pinfunction "9_9") (pintype "passive"))
      (node (ref "U$3") (pin "21/A7") (pinfunction "21/A7/PWM_21/A7") (pintype "bidirectional"))
    )
    (net (code "17") (name "BYPASS") (class "Default")
      (node (ref "AMP") (pin "22") (pinfunction "BYPASS_22") (pintype "bidirectional"))
      (node (ref "C32") (pin "1") (pinfunction "1_1") (pintype "passive"))
    )
    (net (code "18") (name "COSC") (class "Default")
      (node (ref "AMP") (pin "10") (pinfunction "COSC_10") (pintype "bidirectional"))
      (node (ref "C29") (pin "2") (pinfunction "2_2") (pintype "passive"))
    )
    (net (code "19") (name "DIN") (class "Default")
      (node (ref "DIN") (pin "1") (pinfunction "1_1") (pintype "passive"))
      (node (ref "U$3") (pin "22/A8") (pinfunction "22/A8/T/PWM_22/A8") (pintype "bidirectional"))
    )
    (net (code "20") (name "DOUT") (class "Default")
      (node (ref "DOUT") (pin "1") (pinfunction "1_1") (pintype "passive"))
      (node (ref "R2") (pin "2") (pinfunction "2_2") (pintype "passive"))
      (node (ref "U$3") (pin "13") (pinfunction "13/SCK/LED_13") (pintype "bidirectional"))
    )
    (net (code "21") (name "GND") (class "Default")
      (node (ref "AMP") (pin "18") (pinfunction "PGNDR1_18") (pintype "bidirectional"))
      (node (ref "AMP") (pin "19") (pinfunction "PGNDR2_19") (pintype "bidirectional"))
      (node (ref "AMP") (pin "6") (pinfunction "PGNDL1_6") (pintype "bidirectional"))
      (node (ref "AMP") (pin "7") (pinfunction "PGNDL2_7") (pintype "bidirectional"))
      (node (ref "BT2") (pin "GND@1") (pinfunction "-_GND@1") (pintype "power_in"))
      (node (ref "C1") (pin "-") (pinfunction "-_-") (pintype "passive"))
      (node (ref "C10") (pin "2") (pinfunction "2_2") (pintype "passive"))
      (node (ref "C11") (pin "2") (pinfunction "2_2") (pintype "passive"))
      (node (ref "C12") (pin "2") (pinfunction "2_2") (pintype "passive"))
      (node (ref "C13") (pin "2") (pinfunction "2_2") (pintype "passive"))
      (node (ref "C14") (pin "2") (pinfunction "2_2") (pintype "passive"))
      (node (ref "C15") (pin "2") (pinfunction "2_2") (pintype "passive"))
      (node (ref "C16") (pin "2") (pinfunction "2_2") (pintype "passive"))
      (node (ref "C17") (pin "2") (pinfunction "2_2") (pintype "passive"))
      (node (ref "C18") (pin "2") (pinfunction "2_2") (pintype "passive"))
      (node (ref "C19") (pin "2") (pinfunction "2_2") (pintype "passive"))
      (node (ref "C2") (pin "-") (pinfunction "-_-") (pintype "passive"))
      (node (ref "C20") (pin "2") (pinfunction "2_2") (pintype "passive"))
      (node (ref "C21") (pin "2") (pinfunction "2_2") (pintype "passive"))
      (node (ref "C22") (pin "2") (pinfunction "2_2") (pintype "passive"))
      (node (ref "C23") (pin "2") (pinfunction "2_2") (pintype "passive"))
      (node (ref "C24") (pin "2") (pinfunction "2_2") (pintype "passive"))
      (node (ref "C25") (pin "2") (pinfunction "2_2") (pintype "passive"))
      (node (ref "C26") (pin "2") (pinfunction "2_2") (pintype "passive"))
      (node (ref "C27") (pin "2") (pinfunction "2_2") (pintype "passive"))
      (node (ref "C28") (pin "2") (pinfunction "2_2") (pintype "passive"))
      (node (ref "C30") (pin "2") (pinfunction "2_2") (pintype "passive"))
      (node (ref "C31") (pin "2") (pinfunction "2_2") (pintype "passive"))
      (node (ref "C32") (pin "2") (pinfunction "2_2") (pintype "passive"))
      (node (ref "C33") (pin "2") (pinfunction "2_2") (pintype "passive"))
      (node (ref "C34") (pin "2") (pinfunction "2_2") (pintype "passive"))
      (node (ref "C35") (pin "2") (pinfunction "2_2") (pintype "passive"))
      (node (ref "C36") (pin "2") (pinfunction "2_2") (pintype "passive"))
      (node (ref "C37") (pin "2") (pinfunction "2_2") (pintype "passive"))
      (node (ref "C38") (pin "2") (pinfunction "2_2") (pintype "passive"))
      (node (ref "C39") (pin "2") (pinfunction "2_2") (pintype "passive"))
      (node (ref "C40") (pin "2") (pinfunction "2_2") (pintype "passive"))
      (node (ref "C41") (pin "-") (pinfunction "-_-") (pintype "passive"))
      (node (ref "C48") (pin "2") (pinfunction "2_2") (pintype "passive"))
      (node (ref "C49") (pin "2") (pinfunction "2_2") (pintype "passive"))
      (node (ref "C5") (pin "2") (pinfunction "2_2") (pintype "passive"))
      (node (ref "C50") (pin "2") (pinfunction "2_2") (pintype "passive"))
      (node (ref "C57") (pin "2") (pinfunction "2_2") (pintype "passive"))
      (node (ref "C58") (pin "2") (pinfunction "2_2") (pintype "passive"))
      (node (ref "C59") (pin "2") (pinfunction "2_2") (pintype "passive"))
      (node (ref "C6") (pin "2") (pinfunction "2_2") (pintype "passive"))
      (node (ref "C60") (pin "2") (pinfunction "2_2") (pintype "passive"))
      (node (ref "C7") (pin "2") (pinfunction "2_2") (pintype "passive"))
      (node (ref "C8") (pin "2") (pinfunction "2_2") (pintype "passive"))
      (node (ref "C9") (pin "2") (pinfunction "2_2") (pintype "passive"))
      (node (ref "FERRITE2") (pin "1") (pinfunction "1_1") (pintype "passive"))
      (node (ref "J7") (pin "6") (pinfunction "VSS_6") (pintype "passive"))
      (node (ref "J7") (pin "S1") (pinfunction "GND_S1") (pintype "passive"))
      (node (ref "J7") (pin "S2") (pinfunction "GND_S2") (pintype "passive"))
      (node (ref "J7") (pin "S3") (pinfunction "GND_S3") (pintype "passive"))
      (node (ref "J7") (pin "S5") (pinfunction "GND_S5") (pintype "passive"))
      (node (ref "LED1") (pin "3-GND") (pinfunction "GND_3-GND") (pintype "power_in"))
      (node (ref "LED10") (pin "3-GND") (pinfunction "GND_3-GND") (pintype "power_in"))
      (node (ref "LED11") (pin "3-GND") (pinfunction "GND_3-GND") (pintype "power_in"))
      (node (ref "LED12") (pin "3-GND") (pinfunction "GND_3-GND") (pintype "power_in"))
      (node (ref "LED13") (pin "3-GND") (pinfunction "GND_3-GND") (pintype "power_in"))
      (node (ref "LED14") (pin "3-GND") (pinfunction "GND_3-GND") (pintype "power_in"))
      (node (ref "LED15") (pin "3-GND") (pinfunction "GND_3-GND") (pintype "power_in"))
      (node (ref "LED16") (pin "3-GND") (pinfunction "GND_3-GND") (pintype "power_in"))
      (node (ref "LED17") (pin "3-GND") (pinfunction "GND_3-GND") (pintype "power_in"))
      (node (ref "LED18") (pin "3-GND") (pinfunction "GND_3-GND") (pintype "power_in"))
      (node (ref "LED19") (pin "3-GND") (pinfunction "GND_3-GND") (pintype "power_in"))
      (node (ref "LED2") (pin "3-GND") (pinfunction "GND_3-GND") (pintype "power_in"))
      (node (ref "LED20") (pin "3-GND") (pinfunction "GND_3-GND") (pintype "power_in"))
      (node (ref "LED21") (pin "3-GND") (pinfunction "GND_3-GND") (pintype "power_in"))
      (node (ref "LED22") (pin "3-GND") (pinfunction "GND_3-GND") (pintype "power_in"))
      (node (ref "LED23") (pin "3-GND") (pinfunction "GND_3-GND") (pintype "power_in"))
      (node (ref "LED24") (pin "3-GND") (pinfunction "GND_3-GND") (pintype "power_in"))
      (node (ref "LED3") (pin "3-GND") (pinfunction "GND_3-GND") (pintype "power_in"))
      (node (ref "LED4") (pin "3-GND") (pinfunction "GND_3-GND") (pintype "power_in"))
      (node (ref "LED5") (pin "3-GND") (pinfunction "GND_3-GND") (pintype "power_in"))
      (node (ref "LED6") (pin "3-GND") (pinfunction "GND_3-GND") (pintype "power_in"))
      (node (ref "LED7") (pin "3-GND") (pinfunction "GND_3-GND") (pintype "power_in"))
      (node (ref "LED8") (pin "3-GND") (pinfunction "GND_3-GND") (pintype "power_in"))
      (node (ref "LED9") (pin "3-GND") (pinfunction "GND_3-GND") (pintype "power_in"))
      (node (ref "MEMS1") (pin "2") (pinfunction "SELECT_2") (pintype "input"))
      (node (ref "MEMS1") (pin "P$1") (pinfunction "GND_P$1") (pintype "power_in"))
      (node (ref "NEO_PIX2") (pin "3") (pinfunction "3_3") (pintype "passive"))
      (node (ref "PWR_REG") (pin "GND") (pinfunction "GND_GND") (pintype "bidirectional"))
      (node (ref "S1") (pin "1") (pinfunction "1_1") (pintype "passive"))
      (node (ref "S1") (pin "2") (pinfunction "2_2") (pintype "passive"))
      (node (ref "S1") (pin "3") (pinfunction "3_3") (pintype "passive"))
      (node (ref "S1") (pin "4") (pinfunction "4_4") (pintype "passive"))
      (node (ref "S1") (pin "5") (pinfunction "5_5") (pintype "passive"))
      (node (ref "S1") (pin "6") (pinfunction "6_6") (pintype "passive"))
      (node (ref "S1") (pin "7") (pinfunction "7_7") (pintype "passive"))
      (node (ref "S1") (pin "8") (pinfunction "8_8") (pintype "passive"))
      (node (ref "S2") (pin "1") (pinfunction "O_1") (pintype "passive"))
      (node (ref "U$3") (pin "GND") (pinfunction "GND_GND") (pintype "power_in"))
      (node (ref "U$8") (pin "CTRL_ADR0_CS") (pinfunction "ADDR_CTRL_ADR0_CS") (pintype "bidirectional"))
      (node (ref "U$8") (pin "CTRL_MODE") (pinfunction "MODE_CTRL_MODE") (pintype "bidirectional"))
      (node (ref "U$8") (pin "GND1") (pinfunction "GND1_GND1") (pintype "bidirectional"))
      (node (ref "U$8") (pin "GND2") (pinfunction "GND2_GND2") (pintype "bidirectional"))
      (node (ref "U$8") (pin "GND3") (pinfunction "GND3_GND3") (pintype "bidirectional"))
      (node (ref "U$9") (pin "3") (pinfunction "GND_3") (pintype "bidirectional"))
      (node (ref "U2") (pin "4") (pinfunction "VSS_4") (pintype "bidirectional"))
      (node (ref "U2") (pin "5") (pinfunction "VSS_5") (pintype "bidirectional"))
      (node (ref "VEML1") (pin "3") (pinfunction "GND_3") (pintype "bidirectional"))
      (node (ref "VMEL1") (pin "1") (pinfunction "GND_1") (pintype "power_in"))
      (node (ref "VMEL1") (pin "4") (pinfunction "ADDR_4") (pintype "bidirectional"))
    )
    (net (code "22") (name "LINN") (class "Default")
      (node (ref "AMP") (pin "1") (pinfunction "LINN_1") (pintype "bidirectional"))
      (node (ref "C3") (pin "2") (pinfunction "2_2") (pintype "passive"))
    )
    (net (code "23") (name "LOUT_L") (class "Default")
      (node (ref "AMP") (pin "2") (pinfunction "LINP_2") (pintype "bidirectional"))
      (node (ref "C53") (pin "2") (pinfunction "2_2") (pintype "passive"))
    )
    (net (code "24") (name "LOUT_R") (class "Default")
      (node (ref "AMP") (pin "23") (pinfunction "RINP_23") (pintype "bidirectional"))
      (node (ref "C54") (pin "2") (pinfunction "2_2") (pintype "passive"))
    )
    (net (code "25") (name "LRCLK") (class "Default")
      (node (ref "MEMS1") (pin "1") (pinfunction "WS_1") (pintype "input"))
      (node (ref "U$3") (pin "23/A9") (pinfunction "23/A9/T/PWM_23/A9") (pintype "bidirectional"))
      (node (ref "U$8") (pin "I2S_LRCLK") (pinfunction "LRCLK_I2S_LRCLK") (pintype "bidirectional"))
    )
    (net (code "26") (name "MCLK") (class "Default")
      (node (ref "R9") (pin "1") (pinfunction "1_1") (pintype "passive"))
      (node (ref "U$3") (pin "11") (pinfunction "11/MOSI_11") (pintype "bidirectional"))
    )
    (net (code "27") (name "MISO") (class "Default")
      (node (ref "J7") (pin "7") (pinfunction "DAT0_7") (pintype "passive"))
      (node (ref "U$3") (pin "12") (pinfunction "12/MISO_12") (pintype "bidirectional"))
    )
    (net (code "28") (name "MOSI") (class "Default")
      (node (ref "J7") (pin "3") (pinfunction "CMD_3") (pintype "passive"))
      (node (ref "U$3") (pin "7") (pinfunction "7/RX3_7") (pintype "bidirectional"))
    )
    (net (code "29") (name "NEO_PIX1") (class "Default")
      (node (ref "LED1") (pin "4-DIN") (pinfunction "DI_4-DIN") (pintype "input"))
      (node (ref "U$3") (pin "5") (pinfunction "5/PWM_5") (pintype "bidirectional"))
    )
    (net (code "30") (name "NEO_PIX1_OUT") (class "Default")
      (node (ref "LED16") (pin "2-DOUT") (pinfunction "DO_2-DOUT") (pintype "output"))
      (node (ref "LED17") (pin "4-DIN") (pinfunction "DI_4-DIN") (pintype "input"))
    )
    (net (code "31") (name "NEO_PIX2") (class "Default")
      (node (ref "NEO_PIX2") (pin "2") (pinfunction "2_2") (pintype "passive"))
      (node (ref "U$3") (pin "8") (pinfunction "8/TX3_8") (pintype "bidirectional"))
    )
    (net (code "32") (name "Net-(BT1--)") (class "Default")
      (node (ref "BT1") (pin "GND@1") (pinfunction "-_GND@1") (pintype "power_in"))
      (node (ref "BT2") (pin "PWR@1") (pinfunction "+_PWR@1") (pintype "power_in"))
    )
    (net (code "33") (name "Net-(C48-Pad1)") (class "Default")
      (node (ref "C48") (pin "1") (pinfunction "1_1") (pintype "passive"))
      (node (ref "C49") (pin "1") (pinfunction "1_1") (pintype "passive"))
      (node (ref "FERRITE1") (pin "2") (pinfunction "2_2") (pintype "passive"))
      (node (ref "U$8") (pin "VDDA") (pinfunction "VDDA_VDDA") (pintype "bidirectional"))
      (node (ref "U$8") (pin "VDDIO") (pinfunction "VDDIO_VDDIO") (pintype "bidirectional"))
    )
    (net (code "34") (name "Net-(C57-Pad1)") (class "Default")
      (node (ref "C57") (pin "1") (pinfunction "1_1") (pintype "passive"))
      (node (ref "U$8") (pin "VAG") (pinfunction "VAG_VAG") (pintype "bidirectional"))
    )
    (net (code "35") (name "Net-(J1-Pad2)") (class "Default")
      (node (ref "J1") (pin "2") (pinfunction "2_2") (pintype "passive"))
      (node (ref "MIC1") (pin "1") (pinfunction "1_1") (pintype "passive"))
    )
    (net (code "36") (name "Net-(J2-Pad2)") (class "Default")
      (node (ref "J2") (pin "2") (pinfunction "2_2") (pintype "passive"))
      (node (ref "MIC2") (pin "1") (pinfunction "1_1") (pintype "passive"))
    )
    (net (code "37") (name "Net-(J3-Pad2)") (class "Default")
      (node (ref "J3") (pin "2") (pinfunction "2_2") (pintype "passive"))
      (node (ref "MIC3") (pin "1") (pinfunction "1_1") (pintype "passive"))
    )
    (net (code "38") (name "Net-(J4-Pad2)") (class "Default")
      (node (ref "J4") (pin "2") (pinfunction "2_2") (pintype "passive"))
      (node (ref "MIC4") (pin "1") (pinfunction "1_1") (pintype "passive"))
    )
    (net (code "39") (name "Net-(J5-Pad2)") (class "Default")
      (node (ref "J5") (pin "2") (pinfunction "2_2") (pintype "passive"))
      (node (ref "MIC5") (pin "1") (pinfunction "1_1") (pintype "passive"))
    )
    (net (code "40") (name "Net-(J6-Pad2)") (class "Default")
      (node (ref "J6") (pin "2") (pinfunction "2_2") (pintype "passive"))
      (node (ref "MIC1") (pin "2") (pinfunction "2_2") (pintype "passive"))
    )
    (net (code "41") (name "Net-(J8-Pad2)") (class "Default")
      (node (ref "J8") (pin "2") (pinfunction "2_2") (pintype "passive"))
      (node (ref "MIC2") (pin "2") (pinfunction "2_2") (pintype "passive"))
    )
    (net (code "42") (name "Net-(J9-Pad2)") (class "Default")
      (node (ref "J9") (pin "2") (pinfunction "2_2") (pintype "passive"))
      (node (ref "MIC3") (pin "2") (pinfunction "2_2") (pintype "passive"))
    )
    (net (code "43") (name "Net-(J10-Pad2)") (class "Default")
      (node (ref "J10") (pin "2") (pinfunction "2_2") (pintype "passive"))
      (node (ref "MIC4") (pin "2") (pinfunction "2_2") (pintype "passive"))
    )
    (net (code "44") (name "Net-(J11-Pad2)") (class "Default")
      (node (ref "J11") (pin "2") (pinfunction "2_2") (pintype "passive"))
      (node (ref "MIC5") (pin "2") (pinfunction "2_2") (pintype "passive"))
    )
    (net (code "45") (name "Net-(LED1-DO)") (class "Default")
      (node (ref "LED1") (pin "2-DOUT") (pinfunction "DO_2-DOUT") (pintype "output"))
      (node (ref "LED2") (pin "4-DIN") (pinfunction "DI_4-DIN") (pintype "input"))
    )
    (net (code "46") (name "Net-(LED2-DO)") (class "Default")
      (node (ref "LED2") (pin "2-DOUT") (pinfunction "DO_2-DOUT") (pintype "output"))
      (node (ref "LED3") (pin "4-DIN") (pinfunction "DI_4-DIN") (pintype "input"))
    )
    (net (code "47") (name "Net-(LED3-DO)") (class "Default")
      (node (ref "LED3") (pin "2-DOUT") (pinfunction "DO_2-DOUT") (pintype "output"))
      (node (ref "LED4") (pin "4-DIN") (pinfunction "DI_4-DIN") (pintype "input"))
    )
    (net (code "48") (name "Net-(LED4-DO)") (class "Default")
      (node (ref "LED4") (pin "2-DOUT") (pinfunction "DO_2-DOUT") (pintype "output"))
      (node (ref "LED5") (pin "4-DIN") (pinfunction "DI_4-DIN") (pintype "input"))
    )
    (net (code "49") (name "Net-(LED5-DO)") (class "Default")
      (node (ref "LED5") (pin "2-DOUT") (pinfunction "DO_2-DOUT") (pintype "output"))
      (node (ref "LED6") (pin "4-DIN") (pinfunction "DI_4-DIN") (pintype "input"))
    )
    (net (code "50") (name "Net-(LED6-DO)") (class "Default")
      (node (ref "LED6") (pin "2-DOUT") (pinfunction "DO_2-DOUT") (pintype "output"))
      (node (ref "LED7") (pin "4-DIN") (pinfunction "DI_4-DIN") (pintype "input"))
    )
    (net (code "51") (name "Net-(LED7-DO)") (class "Default")
      (node (ref "LED7") (pin "2-DOUT") (pinfunction "DO_2-DOUT") (pintype "output"))
      (node (ref "LED8") (pin "4-DIN") (pinfunction "DI_4-DIN") (pintype "input"))
    )
    (net (code "52") (name "Net-(LED8-DO)") (class "Default")
      (node (ref "LED8") (pin "2-DOUT") (pinfunction "DO_2-DOUT") (pintype "output"))
      (node (ref "LED9") (pin "4-DIN") (pinfunction "DI_4-DIN") (pintype "input"))
    )
    (net (code "53") (name "Net-(LED10-DI)") (class "Default")
      (node (ref "LED10") (pin "4-DIN") (pinfunction "DI_4-DIN") (pintype "input"))
      (node (ref "LED9") (pin "2-DOUT") (pinfunction "DO_2-DOUT") (pintype "output"))
    )
    (net (code "54") (name "Net-(LED10-DO)") (class "Default")
      (node (ref "LED10") (pin "2-DOUT") (pinfunction "DO_2-DOUT") (pintype "output"))
      (node (ref "LED11") (pin "4-DIN") (pinfunction "DI_4-DIN") (pintype "input"))
    )
    (net (code "55") (name "Net-(LED11-DO)") (class "Default")
      (node (ref "LED11") (pin "2-DOUT") (pinfunction "DO_2-DOUT") (pintype "output"))
      (node (ref "LED12") (pin "4-DIN") (pinfunction "DI_4-DIN") (pintype "input"))
    )
    (net (code "56") (name "Net-(LED12-DO)") (class "Default")
      (node (ref "LED12") (pin "2-DOUT") (pinfunction "DO_2-DOUT") (pintype "output"))
      (node (ref "LED13") (pin "4-DIN") (pinfunction "DI_4-DIN") (pintype "input"))
    )
    (net (code "57") (name "Net-(LED13-DO)") (class "Default")
      (node (ref "LED13") (pin "2-DOUT") (pinfunction "DO_2-DOUT") (pintype "output"))
      (node (ref "LED14") (pin "4-DIN") (pinfunction "DI_4-DIN") (pintype "input"))
    )
    (net (code "58") (name "Net-(LED14-DO)") (class "Default")
      (node (ref "LED14") (pin "2-DOUT") (pinfunction "DO_2-DOUT") (pintype "output"))
      (node (ref "LED15") (pin "4-DIN") (pinfunction "DI_4-DIN") (pintype "input"))
    )
    (net (code "59") (name "Net-(LED15-DO)") (class "Default")
      (node (ref "LED15") (pin "2-DOUT") (pinfunction "DO_2-DOUT") (pintype "output"))
      (node (ref "LED16") (pin "4-DIN") (pinfunction "DI_4-DIN") (pintype "input"))
    )
    (net (code "60") (name "Net-(LED17-DO)") (class "Default")
      (node (ref "LED17") (pin "2-DOUT") (pinfunction "DO_2-DOUT") (pintype "output"))
      (node (ref "LED18") (pin "4-DIN") (pinfunction "DI_4-DIN") (pintype "input"))
    )
    (net (code "61") (name "Net-(LED18-DO)") (class "Default")
      (node (ref "LED18") (pin "2-DOUT") (pinfunction "DO_2-DOUT") (pintype "output"))
      (node (ref "LED19") (pin "4-DIN") (pinfunction "DI_4-DIN") (pintype "input"))
    )
    (net (code "62") (name "Net-(LED19-DO)") (class "Default")
      (node (ref "LED19") (pin "2-DOUT") (pinfunction "DO_2-DOUT") (pintype "output"))
      (node (ref "LED20") (pin "4-DIN") (pinfunction "DI_4-DIN") (pintype "input"))
    )
    (net (code "63") (name "Net-(LED20-DO)") (class "Default")
      (node (ref "LED20") (pin "2-DOUT") (pinfunction "DO_2-DOUT") (pintype "output"))
      (node (ref "LED21") (pin "4-DIN") (pinfunction "DI_4-DIN") (pintype "input"))
    )
    (net (code "64") (name "Net-(LED21-DO)") (class "Default")
      (node (ref "LED21") (pin "2-DOUT") (pinfunction "DO_2-DOUT") (pintype "output"))
      (node (ref "LED22") (pin "4-DIN") (pinfunction "DI_4-DIN") (pintype "input"))
    )
    (net (code "65") (name "Net-(LED22-DO)") (class "Default")
      (node (ref "LED22") (pin "2-DOUT") (pinfunction "DO_2-DOUT") (pintype "output"))
      (node (ref "LED23") (pin "4-DIN") (pinfunction "DI_4-DIN") (pintype "input"))
    )
    (net (code "66") (name "Net-(LED23-DO)") (class "Default")
      (node (ref "LED23") (pin "2-DOUT") (pinfunction "DO_2-DOUT") (pintype "output"))
      (node (ref "LED24") (pin "4-DIN") (pinfunction "DI_4-DIN") (pintype "input"))
    )
    (net (code "67") (name "Net-(MEMS1-DATA_OUT)") (class "Default")
      (node (ref "MEMS1") (pin "6") (pinfunction "DATA_OUT_6") (pintype "output"))
      (node (ref "R2") (pin "1") (pinfunction "1_1") (pintype "passive"))
    )
    (net (code "68") (name "Net-(S2-P)") (class "Default")
      (node (ref "PWR_REG") (pin "EN") (pinfunction "EN_EN") (pintype "bidirectional"))
      (node (ref "S2") (pin "2") (pinfunction "P_2") (pintype "passive"))
    )
    (net (code "69") (name "Net-(U$8-LINEOUTL)") (class "Default")
      (node (ref "C54") (pin "1") (pinfunction "1_1") (pintype "passive"))
      (node (ref "U$8") (pin "LINEOUT_L") (pinfunction "LINEOUTL_LINEOUT_L") (pintype "bidirectional"))
    )
    (net (code "70") (name "Net-(U$8-LINEOUTR)") (class "Default")
      (node (ref "C53") (pin "1") (pinfunction "1_1") (pintype "passive"))
      (node (ref "U$8") (pin "LINEOUT_R") (pinfunction "LINEOUTR_LINEOUT_R") (pintype "bidirectional"))
    )
    (net (code "71") (name "Net-(U$8-MCLK)") (class "Default")
      (node (ref "R9") (pin "2") (pinfunction "2_2") (pintype "passive"))
      (node (ref "U$8") (pin "SYS_MCLK") (pinfunction "MCLK_SYS_MCLK") (pintype "bidirectional"))
    )
    (net (code "72") (name "Net-(U$8-RX)") (class "Default")
      (node (ref "DIN") (pin "2") (pinfunction "2_2") (pintype "passive"))
      (node (ref "U$8") (pin "I2S_DIN") (pinfunction "RX_I2S_DIN") (pintype "bidirectional"))
    )
    (net (code "73") (name "Net-(U$8-TX)") (class "Default")
      (node (ref "DOUT") (pin "2") (pinfunction "2_2") (pintype "passive"))
      (node (ref "U$8") (pin "I2S_DOUT") (pinfunction "TX_I2S_DOUT") (pintype "bidirectional"))
    )
    (net (code "74") (name "Net-(U$9-OUT)") (class "Default")
      (node (ref "C50") (pin "1") (pinfunction "1_1") (pintype "passive"))
      (node (ref "U$8") (pin "VDDD") (pinfunction "VDDD_VDDD") (pintype "bidirectional"))
      (node (ref "U$9") (pin "2") (pinfunction "OUT_2") (pintype "bidirectional"))
    )
    (net (code "75") (name "Net-(VEML1-VDD)") (class "Default")
      (node (ref "C10") (pin "1") (pinfunction "1_1") (pintype "passive"))
      (node (ref "C8") (pin "1") (pinfunction "1_1") (pintype "passive"))
      (node (ref "R1") (pin "1") (pinfunction "1_1") (pintype "passive"))
      (node (ref "VEML1") (pin "2") (pinfunction "VDD_2") (pintype "bidirectional"))
      (node (ref "VMEL1") (pin "6") (pinfunction "VDD_6") (pintype "power_in"))
    )
    (net (code "76") (name "POT1") (class "Default")
      (node (ref "U$3") (pin "17/A3") (pinfunction "17/A3/T_17/A3") (pintype "bidirectional"))
      (node (ref "U$4") (pin "P$1") (pinfunction "P$1_P$1") (pintype "bidirectional"))
    )
    (net (code "77") (name "RINN") (class "Default")
      (node (ref "AMP") (pin "24") (pinfunction "RINN_24") (pintype "bidirectional"))
      (node (ref "C4") (pin "2") (pinfunction "2_2") (pintype "passive"))
    )
    (net (code "78") (name "ROSC") (class "Default")
      (node (ref "AMP") (pin "11") (pinfunction "ROSC_11") (pintype "bidirectional"))
      (node (ref "R5") (pin "2") (pinfunction "2_2") (pintype "passive"))
    )
    (net (code "79") (name "SCL") (class "Default")
      (node (ref "R4") (pin "1") (pinfunction "1_1") (pintype "passive"))
      (node (ref "U$3") (pin "19/A5") (pinfunction "19/A5/T/SCL0_19/A5") (pintype "bidirectional"))
      (node (ref "U$8") (pin "CTRL_CLK") (pinfunction "SCL_CTRL_CLK") (pintype "bidirectional"))
      (node (ref "U2") (pin "2") (pinfunction "SCL_2") (pintype "bidirectional"))
      (node (ref "VEML1") (pin "1") (pinfunction "SCL_1") (pintype "bidirectional"))
      (node (ref "VMEL1") (pin "5") (pinfunction "SCL_5") (pintype "input"))
    )
    (net (code "80") (name "SDA") (class "Default")
      (node (ref "R3") (pin "1") (pinfunction "1_1") (pintype "passive"))
      (node (ref "U$3") (pin "18/A4") (pinfunction "18/A4/T/SDA0_18/A4") (pintype "bidirectional"))
      (node (ref "U$8") (pin "CTRL_DATA") (pinfunction "SDA_CTRL_DATA") (pintype "bidirectional"))
      (node (ref "U2") (pin "3") (pinfunction "SDA_3") (pintype "bidirectional"))
      (node (ref "VEML1") (pin "4") (pinfunction "SDA_4") (pintype "bidirectional"))
      (node (ref "VMEL1") (pin "2") (pinfunction "SDA_2") (pintype "bidirectional"))
    )
    (net (code "81") (name "SD_CS") (class "Default")
      (node (ref "J7") (pin "2") (pinfunction "CD/DAT3_2") (pintype "passive"))
      (node (ref "R11") (pin "1") (pinfunction "1_1") (pintype "passive"))
      (node (ref "U$3") (pin "10") (pinfunction "10/TX2/PWM_10") (pintype "bidirectional"))
    )
    (net (code "82") (name "SPI_CLK") (class "Default")
      (node (ref "J7") (pin "5") (pinfunction "CLK_5") (pintype "passive"))
      (node (ref "U$3") (pin "14/A0") (pinfunction "14/A1_14/A0") (pintype "bidirectional"))
    )
    (net (code "83") (name "TPA_SHDN") (class "Default")
      (node (ref "AMP") (pin "3") (pinfunction "SHDN_3") (pintype "bidirectional"))
      (node (ref "U$3") (pin "3") (pinfunction "3/CAN-TX/PWM_3") (pintype "bidirectional"))
    )
    (net (code "84") (name "VEML_INT") (class "Default")
      (node (ref "U$3") (pin "2") (pinfunction "2_2") (pintype "bidirectional"))
      (node (ref "VMEL1") (pin "3") (pinfunction "INT_3") (pintype "output"))
    )
    (net (code "85") (name "VIN") (class "Default")
      (node (ref "BT1") (pin "PWR@1") (pinfunction "+_PWR@1") (pintype "power_in"))
      (node (ref "C2") (pin "+") (pinfunction "+_+") (pintype "passive"))
      (node (ref "PWR_REG") (pin "VIN") (pinfunction "VIN_VIN") (pintype "bidirectional"))
    )
    (net (code "86") (name "VOL") (class "Default")
      (node (ref "AMP") (pin "14") (pinfunction "VOL_14") (pintype "bidirectional"))
      (node (ref "U$6") (pin "P$1") (pinfunction "P$1_P$1") (pintype "bidirectional"))
    )
    (net (code "87") (name "_BUT1") (class "Default")
      (node (ref "DIN1") (pin "2") (pinfunction "2_2") (pintype "passive"))
      (node (ref "S1") (pin "16") (pinfunction "16_16") (pintype "passive"))
    )
    (net (code "88") (name "_BUT2") (class "Default")
      (node (ref "DIN2") (pin "2") (pinfunction "2_2") (pintype "passive"))
      (node (ref "S1") (pin "15") (pinfunction "15_15") (pintype "passive"))
    )
    (net (code "89") (name "unconnected-(AMP-NC-Pad15)") (class "Default")
      (node (ref "AMP") (pin "15") (pinfunction "NC_15") (pintype "bidirectional"))
    )
    (net (code "90") (name "unconnected-(J7-CD_SW-Pad9)") (class "Default")
      (node (ref "J7") (pin "9") (pinfunction "CD_SW_9") (pintype "passive"))
    )
    (net (code "91") (name "unconnected-(J7-DAT1-Pad8)") (class "Default")
      (node (ref "J7") (pin "8") (pinfunction "DAT1_8") (pintype "passive"))
    )
    (net (code "92") (name "unconnected-(J7-DAT2-Pad1)") (class "Default")
      (node (ref "J7") (pin "1") (pinfunction "DAT2_1") (pintype "passive"))
    )
    (net (code "93") (name "unconnected-(LED24-DO-Pad2-DOUT)") (class "Default")
      (node (ref "LED24") (pin "2-DOUT") (pinfunction "DO_2-DOUT") (pintype "output"))
    )
    (net (code "94") (name "unconnected-(PWR_REG-PadPG)") (class "Default")
      (node (ref "PWR_REG") (pin "PG") (pinfunction "PG_PG") (pintype "bidirectional"))
    )
    (net (code "95") (name "unconnected-(PWR_REG-PadSEL)") (class "Default")
      (node (ref "PWR_REG") (pin "SEL") (pinfunction "SEL_SEL") (pintype "bidirectional"))
    )
    (net (code "96") (name "unconnected-(S2-S-Pad3)") (class "Default")
      (node (ref "S2") (pin "3") (pinfunction "S_3") (pintype "passive"))
    )
    (net (code "97") (name "unconnected-(U$8-HPL-PadHP_L)") (class "Default")
      (node (ref "U$8") (pin "HP_L") (pinfunction "HPL_HP_L") (pintype "bidirectional"))
    )
    (net (code "98") (name "unconnected-(U$8-HPR-PadHP_R)") (class "Default")
      (node (ref "U$8") (pin "HP_R") (pinfunction "HPR_HP_R") (pintype "bidirectional"))
    )
    (net (code "99") (name "unconnected-(U$8-HPVGND-PadHP_VGND)") (class "Default")
      (node (ref "U$8") (pin "HP_VGND") (pinfunction "HPVGND_HP_VGND") (pintype "bidirectional"))
    )
    (net (code "100") (name "unconnected-(U$8-LINEINL-PadLININ_L)") (class "Default")
      (node (ref "U$8") (pin "LININ_L") (pinfunction "LINEINL_LININ_L") (pintype "bidirectional"))
    )
    (net (code "101") (name "unconnected-(U$8-LINEINR-PadLININ_R)") (class "Default")
      (node (ref "U$8") (pin "LININ_R") (pinfunction "LINEINR_LININ_R") (pintype "bidirectional"))
    )
    (net (code "102") (name "unconnected-(U$8-MICBIAS-PadMIC_BIAS)") (class "Default")
      (node (ref "U$8") (pin "MIC_BIAS") (pinfunction "MICBIAS_MIC_BIAS") (pintype "bidirectional"))
    )
    (net (code "103") (name "unconnected-(U$8-PadCPFILT)") (class "Default")
      (node (ref "U$8") (pin "CPFILT") (pinfunction "CPFILT_CPFILT") (pintype "bidirectional"))
    )
    (net (code "104") (name "unconnected-(U$8-PadMIC)") (class "Default")
      (node (ref "U$8") (pin "MIC") (pinfunction "MIC_MIC") (pintype "bidirectional"))
    )
  )
)
